# G879A.net
KiCad netlist of a schematic drawn in EAGLE
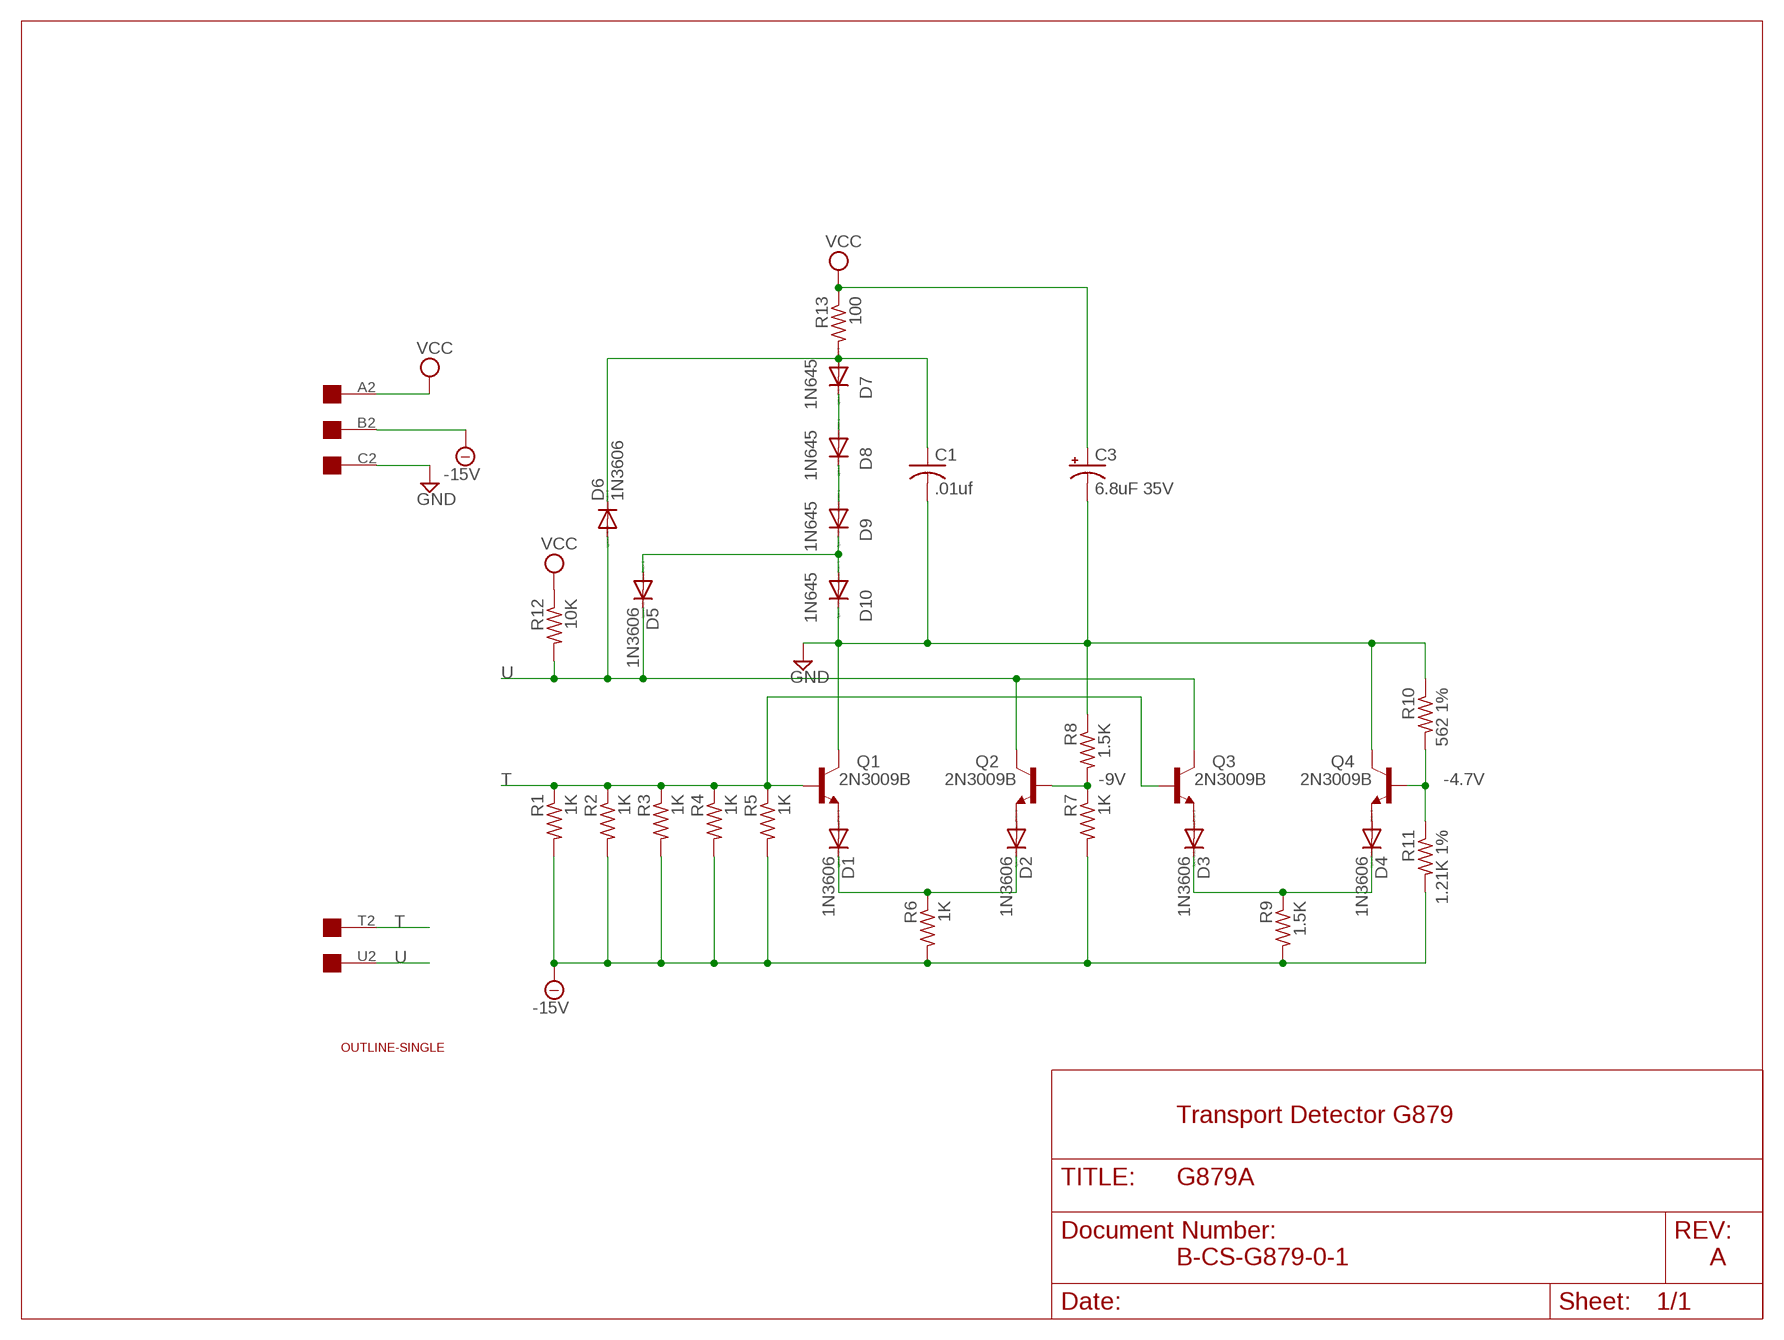
[diagram p0: schematic, sheet 1]

(export (version "E")
  (design (tool "Eeschema 10.0.6"))
  (components
    (comp (ref "C1")
      (value ".01uf")
      (footprint "eagle-import:C050-025X075")
      (libsource (lib "eagle-import") (part "C-US050-025X075"))
    )
    (comp (ref "C3")
      (value "6.8uF 35V")
      (footprint "eagle-import:E12-8")
      (libsource (lib "eagle-import") (part "CPOL-USE20-8AXIAL"))
    )
    (comp (ref "D1")
      (value "1N3606")
      (footprint "eagle-import:DO41-10")
      (libsource (lib "eagle-import") (part "1N4004"))
    )
    (comp (ref "D2")
      (value "1N3606")
      (footprint "eagle-import:DO41-10")
      (libsource (lib "eagle-import") (part "1N4004"))
    )
    (comp (ref "D3")
      (value "1N3606")
      (footprint "eagle-import:DO41-10")
      (libsource (lib "eagle-import") (part "1N4004"))
    )
    (comp (ref "D4")
      (value "1N3606")
      (footprint "eagle-import:DO41-10")
      (libsource (lib "eagle-import") (part "1N4004"))
    )
    (comp (ref "D5")
      (value "1N3606")
      (footprint "eagle-import:DO41-10")
      (libsource (lib "eagle-import") (part "1N4004"))
    )
    (comp (ref "D6")
      (value "1N3606")
      (footprint "eagle-import:DO41-10")
      (libsource (lib "eagle-import") (part "1N4004"))
    )
    (comp (ref "D7")
      (value "1N645")
      (footprint "eagle-import:DO41-10")
      (libsource (lib "eagle-import") (part "1N4004"))
    )
    (comp (ref "D8")
      (value "1N645")
      (footprint "eagle-import:DO41-10")
      (libsource (lib "eagle-import") (part "1N4004"))
    )
    (comp (ref "D9")
      (value "1N645")
      (footprint "eagle-import:DO41-10")
      (libsource (lib "eagle-import") (part "1N4004"))
    )
    (comp (ref "D10")
      (value "1N645")
      (footprint "eagle-import:DO41-10")
      (libsource (lib "eagle-import") (part "1N4004"))
    )
    (comp (ref "Q1")
      (value "2N3009B")
      (footprint "eagle-import:TO39")
      (libsource (lib "eagle-import") (part "2N1711"))
    )
    (comp (ref "Q2")
      (value "2N3009B")
      (footprint "eagle-import:TO39")
      (libsource (lib "eagle-import") (part "2N1711"))
    )
    (comp (ref "Q3")
      (value "2N3009B")
      (footprint "eagle-import:TO39")
      (libsource (lib "eagle-import") (part "2N1711"))
    )
    (comp (ref "Q4")
      (value "2N3009B")
      (footprint "eagle-import:TO39")
      (libsource (lib "eagle-import") (part "2N1711"))
    )
    (comp (ref "R1")
      (value "1K")
      (footprint "eagle-import:0207_10")
      (libsource (lib "eagle-import") (part "R-US_0207/10"))
    )
    (comp (ref "R2")
      (value "1K")
      (footprint "eagle-import:0207_10")
      (libsource (lib "eagle-import") (part "R-US_0207/10"))
    )
    (comp (ref "R3")
      (value "1K")
      (footprint "eagle-import:0207_10")
      (libsource (lib "eagle-import") (part "R-US_0207/10"))
    )
    (comp (ref "R4")
      (value "1K")
      (footprint "eagle-import:0207_10")
      (libsource (lib "eagle-import") (part "R-US_0207/10"))
    )
    (comp (ref "R5")
      (value "1K")
      (footprint "eagle-import:0207_10")
      (libsource (lib "eagle-import") (part "R-US_0207/10"))
    )
    (comp (ref "R6")
      (value "1K")
      (footprint "eagle-import:0207_10")
      (libsource (lib "eagle-import") (part "R-US_0207/10"))
    )
    (comp (ref "R7")
      (value "1K")
      (footprint "eagle-import:0207_10")
      (libsource (lib "eagle-import") (part "R-US_0207/10"))
    )
    (comp (ref "R8")
      (value "1.5K")
      (footprint "eagle-import:0207_10")
      (libsource (lib "eagle-import") (part "R-US_0207/10"))
    )
    (comp (ref "R9")
      (value "1.5K")
      (footprint "eagle-import:0207_10")
      (libsource (lib "eagle-import") (part "R-US_0207/10"))
    )
    (comp (ref "R10")
      (value "562 1%")
      (footprint "eagle-import:0207_15")
      (libsource (lib "eagle-import") (part "R-US_0207/15"))
    )
    (comp (ref "R11")
      (value "1.21K 1%")
      (footprint "eagle-import:0207_15")
      (libsource (lib "eagle-import") (part "R-US_0207/15"))
    )
    (comp (ref "R12")
      (value "10K")
      (footprint "eagle-import:0207_10")
      (libsource (lib "eagle-import") (part "R-US_0207/10"))
    )
    (comp (ref "R13")
      (value "100")
      (footprint "eagle-import:0207_10")
      (libsource (lib "eagle-import") (part "R-US_0207/10"))
    )
    (comp (ref "U$1")
      (value "EDGE-1")
      (footprint "eagle-import:EDGE-CON1")
      (libsource (lib "eagle-import") (part "EDGE-1"))
    )
    (comp (ref "U$2")
      (value "OUTLINE-SINGLE")
      (footprint "eagle-import:SINGLE")
      (libsource (lib "eagle-import") (part "OUTLINE-SINGLE"))
    )
  )
  (nets
    (net (code "1") (name "-15V") (class "Default")
      (node (ref "R1") (pin "2") (pinfunction "2_2") (pintype "passive"))
      (node (ref "R11") (pin "2") (pinfunction "2_2") (pintype "passive"))
      (node (ref "R2") (pin "2") (pinfunction "2_2") (pintype "passive"))
      (node (ref "R3") (pin "2") (pinfunction "2_2") (pintype "passive"))
      (node (ref "R4") (pin "2") (pinfunction "2_2") (pintype "passive"))
      (node (ref "R5") (pin "2") (pinfunction "2_2") (pintype "passive"))
      (node (ref "R6") (pin "2") (pinfunction "2_2") (pintype "passive"))
      (node (ref "R7") (pin "2") (pinfunction "2_2") (pintype "passive"))
      (node (ref "R9") (pin "2") (pinfunction "2_2") (pintype "passive"))
      (node (ref "U$1") (pin "B2") (pinfunction "1_B2") (pintype "bidirectional"))
    )
    (net (code "2") (name "/-4.7V") (class "Default")
      (node (ref "Q4") (pin "2") (pinfunction "B_2") (pintype "passive"))
      (node (ref "R10") (pin "2") (pinfunction "2_2") (pintype "passive"))
      (node (ref "R11") (pin "1") (pinfunction "1_1") (pintype "passive"))
    )
    (net (code "3") (name "/-9V") (class "Default")
      (node (ref "Q2") (pin "2") (pinfunction "B_2") (pintype "passive"))
      (node (ref "R7") (pin "1") (pinfunction "1_1") (pintype "passive"))
      (node (ref "R8") (pin "2") (pinfunction "2_2") (pintype "passive"))
    )
    (net (code "4") (name "/T") (class "Default")
      (node (ref "Q1") (pin "2") (pinfunction "B_2") (pintype "passive"))
      (node (ref "Q3") (pin "2") (pinfunction "B_2") (pintype "passive"))
      (node (ref "R1") (pin "1") (pinfunction "1_1") (pintype "passive"))
      (node (ref "R2") (pin "1") (pinfunction "1_1") (pintype "passive"))
      (node (ref "R3") (pin "1") (pinfunction "1_1") (pintype "passive"))
      (node (ref "R4") (pin "1") (pinfunction "1_1") (pintype "passive"))
      (node (ref "R5") (pin "1") (pinfunction "1_1") (pintype "passive"))
      (node (ref "U$1") (pin "T2") (pinfunction "1_T2") (pintype "bidirectional"))
    )
    (net (code "5") (name "/U") (class "Default")
      (node (ref "D5") (pin "C") (pinfunction "C_C") (pintype "passive"))
      (node (ref "D6") (pin "A") (pinfunction "A_A") (pintype "passive"))
      (node (ref "Q2") (pin "3") (pinfunction "C_3") (pintype "passive"))
      (node (ref "Q3") (pin "3") (pinfunction "C_3") (pintype "passive"))
      (node (ref "R12") (pin "2") (pinfunction "2_2") (pintype "passive"))
      (node (ref "U$1") (pin "U2") (pinfunction "1_U2") (pintype "bidirectional"))
    )
    (net (code "6") (name "GND") (class "Default")
      (node (ref "C1") (pin "2") (pinfunction "2_2") (pintype "passive"))
      (node (ref "C3") (pin "-") (pinfunction "-_-") (pintype "passive"))
      (node (ref "D10") (pin "C") (pinfunction "C_C") (pintype "passive"))
      (node (ref "Q1") (pin "3") (pinfunction "C_3") (pintype "passive"))
      (node (ref "Q4") (pin "3") (pinfunction "C_3") (pintype "passive"))
      (node (ref "R10") (pin "1") (pinfunction "1_1") (pintype "passive"))
      (node (ref "R8") (pin "1") (pinfunction "1_1") (pintype "passive"))
      (node (ref "U$1") (pin "C2") (pinfunction "1_C2") (pintype "bidirectional"))
    )
    (net (code "7") (name "Net-(C1-Pad1)") (class "Default")
      (node (ref "C1") (pin "1") (pinfunction "1_1") (pintype "passive"))
      (node (ref "D6") (pin "C") (pinfunction "C_C") (pintype "passive"))
      (node (ref "D7") (pin "A") (pinfunction "A_A") (pintype "passive"))
      (node (ref "R13") (pin "2") (pinfunction "2_2") (pintype "passive"))
    )
    (net (code "8") (name "Net-(D1-PadC)") (class "Default")
      (node (ref "D1") (pin "C") (pinfunction "C_C") (pintype "passive"))
      (node (ref "D2") (pin "C") (pinfunction "C_C") (pintype "passive"))
      (node (ref "R6") (pin "1") (pinfunction "1_1") (pintype "passive"))
    )
    (net (code "9") (name "Net-(D3-PadC)") (class "Default")
      (node (ref "D3") (pin "C") (pinfunction "C_C") (pintype "passive"))
      (node (ref "D4") (pin "C") (pinfunction "C_C") (pintype "passive"))
      (node (ref "R9") (pin "1") (pinfunction "1_1") (pintype "passive"))
    )
    (net (code "10") (name "Net-(D7-PadC)") (class "Default")
      (node (ref "D7") (pin "C") (pinfunction "C_C") (pintype "passive"))
      (node (ref "D8") (pin "A") (pinfunction "A_A") (pintype "passive"))
    )
    (net (code "11") (name "Net-(D8-PadC)") (class "Default")
      (node (ref "D8") (pin "C") (pinfunction "C_C") (pintype "passive"))
      (node (ref "D9") (pin "A") (pinfunction "A_A") (pintype "passive"))
    )
    (net (code "12") (name "Net-(D10-PadA)") (class "Default")
      (node (ref "D10") (pin "A") (pinfunction "A_A") (pintype "passive"))
      (node (ref "D5") (pin "A") (pinfunction "A_A") (pintype "passive"))
      (node (ref "D9") (pin "C") (pinfunction "C_C") (pintype "passive"))
    )
    (net (code "13") (name "Net-(Q1-E)") (class "Default")
      (node (ref "D1") (pin "A") (pinfunction "A_A") (pintype "passive"))
      (node (ref "Q1") (pin "1") (pinfunction "E_1") (pintype "passive"))
    )
    (net (code "14") (name "Net-(Q2-E)") (class "Default")
      (node (ref "D2") (pin "A") (pinfunction "A_A") (pintype "passive"))
      (node (ref "Q2") (pin "1") (pinfunction "E_1") (pintype "passive"))
    )
    (net (code "15") (name "Net-(Q3-E)") (class "Default")
      (node (ref "D3") (pin "A") (pinfunction "A_A") (pintype "passive"))
      (node (ref "Q3") (pin "1") (pinfunction "E_1") (pintype "passive"))
    )
    (net (code "16") (name "Net-(Q4-E)") (class "Default")
      (node (ref "D4") (pin "A") (pinfunction "A_A") (pintype "passive"))
      (node (ref "Q4") (pin "1") (pinfunction "E_1") (pintype "passive"))
    )
    (net (code "17") (name "VCC") (class "Default")
      (node (ref "C3") (pin "+") (pinfunction "+_+") (pintype "passive"))
      (node (ref "R12") (pin "1") (pinfunction "1_1") (pintype "passive"))
      (node (ref "R13") (pin "1") (pinfunction "1_1") (pintype "passive"))
      (node (ref "U$1") (pin "A2") (pinfunction "1_A2") (pintype "bidirectional"))
    )
  )
)
